# ProPrj___2025-12-14-16-01-24.net
KiCad netlist of a schematic drawn in EasyEDA Pro
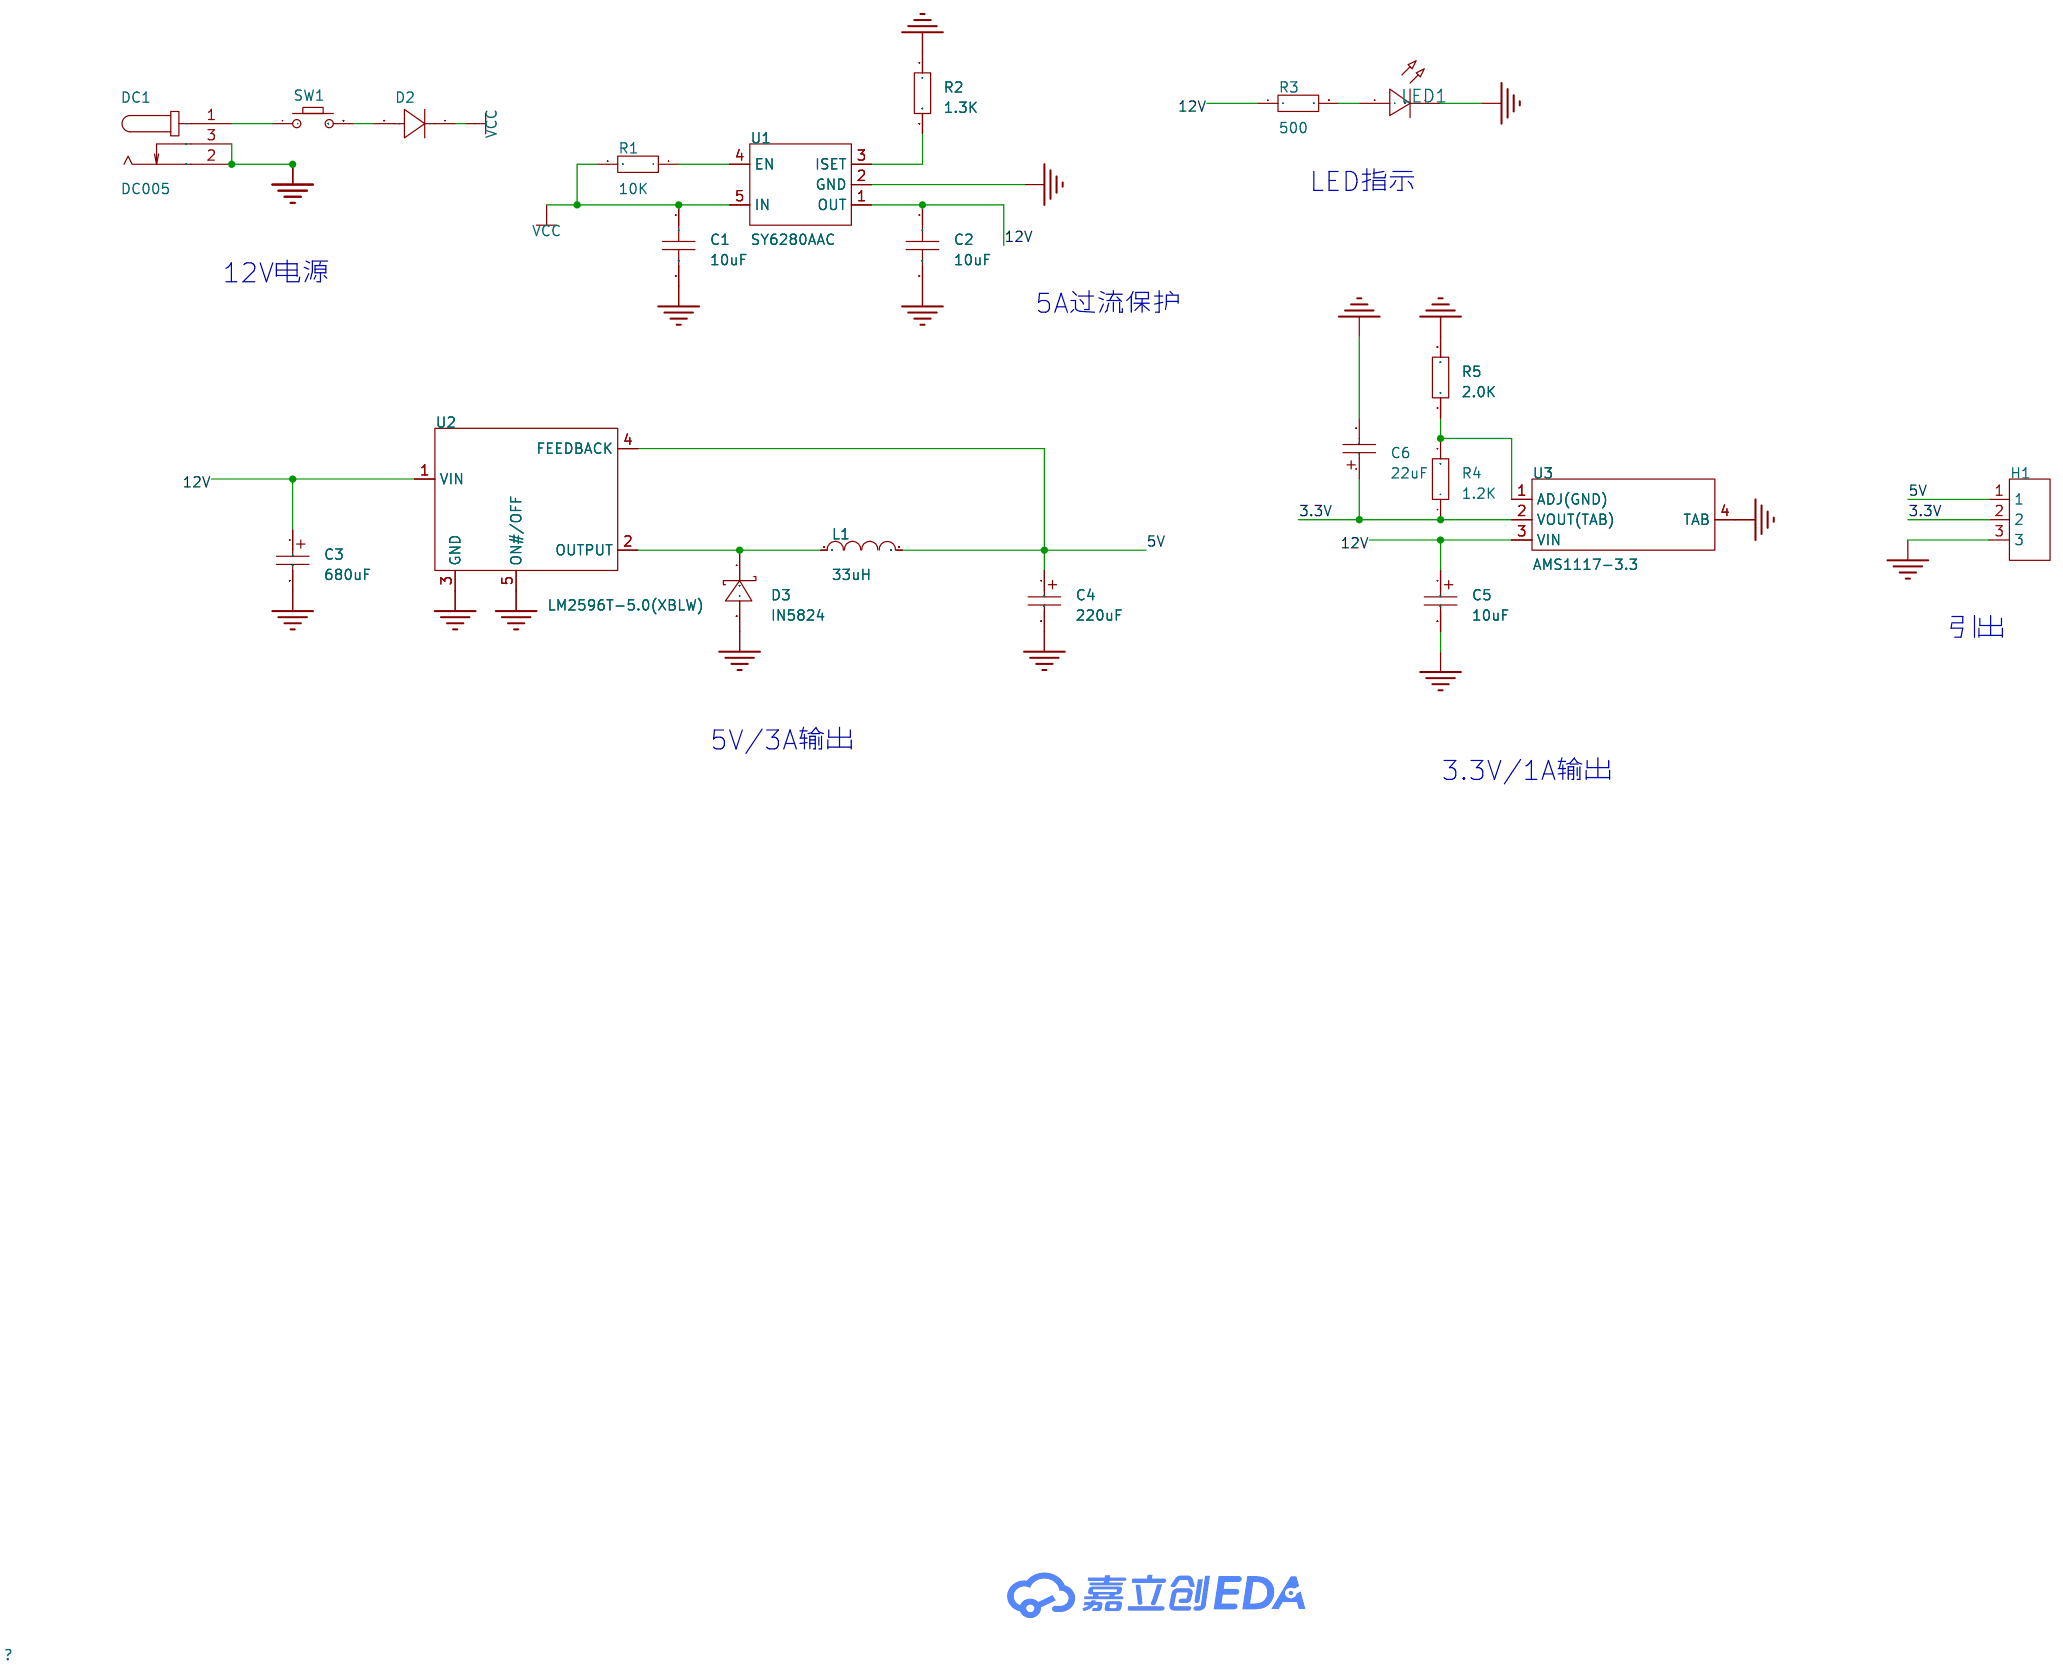
[diagram p0: schematic sheet]

(export (version "E")
  (design (tool "Eeschema 10.0.6"))
  (components
    (comp (ref "C1")
      (value "10uF")
      (footprint "easyedapro:C0603")
      (libsource (lib "easyedapro") (part "Capacitance"))
    )
    (comp (ref "C2")
      (value "10uF")
      (footprint "easyedapro:C0603")
      (libsource (lib "easyedapro") (part "Capacitance"))
    )
    (comp (ref "C3")
      (value "680uF")
      (footprint "easyedapro:C_Ele_SMD_3x5.4mm")
      (libsource (lib "easyedapro") (part "CAP"))
    )
    (comp (ref "C4")
      (value "220uF")
      (footprint "easyedapro:C_Ele_SMD_3x5.4mm")
      (libsource (lib "easyedapro") (part "CAP"))
    )
    (comp (ref "C5")
      (value "10uF")
      (footprint "easyedapro:C_Ele_SMD_3x5.4mm")
      (libsource (lib "easyedapro") (part "CAP"))
    )
    (comp (ref "C6")
      (value "22uF")
      (footprint "easyedapro:C_Ele_SMD_3x5.4mm")
      (libsource (lib "easyedapro") (part "CAP"))
    )
    (comp (ref "D2")
      (value "~")
      (footprint "easyedapro:DO_1N4007")
      (libsource (lib "easyedapro") (part "D_1N4007"))
    )
    (comp (ref "D3")
      (value "IN5824")
      (footprint "easyedapro:SMAF_L3.5-W2.6-LS4.7-RD")
      (libsource (lib "easyedapro") (part "IN5824"))
    )
    (comp (ref "DC1")
      (value "DC005")
      (footprint "easyedapro:DC-IN-TH_DC005")
      (description "连接器类型:DC电源插座;安装方式:弯插;触点内径:2mm;触点外径:6.3mm;额定电流:500mA;额定电压:12V;工作温度:-30°C~+70°C;")
      (fields (field (name "Manufacturer") "SHOU HAN(首韩)"))
      (libsource (lib "easyedapro") (part "DC005_C431533"))
    )
    (comp (ref "H1")
      (value "~")
      (footprint "easyedapro:HDR-TH_3P-P2.54-V-F")
      (libsource (lib "easyedapro") (part "PM254V-11-03-H85"))
    )
    (comp (ref "L1")
      (value "33uH")
      (footprint "easyedapro:L0603")
      (libsource (lib "easyedapro") (part "SDFL1608S100KTF"))
    )
    (comp (ref "LED1")
      (value "~")
      (footprint "easyedapro:LED_0603")
      (libsource (lib "easyedapro") (part "LED_R"))
    )
    (comp (ref "R1") (value "10K") (footprint "easyedapro:R0603") (libsource (lib "easyedapro") (part "电阻")))
    (comp (ref "R2") (value "1.3K") (footprint "easyedapro:R0603") (libsource (lib "easyedapro") (part "电阻")))
    (comp (ref "R3") (value "500") (footprint "easyedapro:R0603") (libsource (lib "easyedapro") (part "电阻")))
    (comp (ref "R4") (value "1.2K") (footprint "easyedapro:R0603") (libsource (lib "easyedapro") (part "电阻")))
    (comp (ref "R5") (value "2.0K") (footprint "easyedapro:R0603") (libsource (lib "easyedapro") (part "电阻")))
    (comp (ref "SW1")
      (value "~")
      (footprint "easyedapro:Key_TH_3.5x6x4.3")
      (libsource (lib "easyedapro") (part "Key_TH_3.5x6x4.3"))
    )
    (comp (ref "U1")
      (value "SY6280AAC")
      (footprint "easyedapro:SOT-23-5_L3.0-W1.7-P0.95-LS2.8-BR")
      (libsource (lib "easyedapro") (part "SY6280AAC_C9900003867"))
    )
    (comp (ref "U2")
      (value "LM2596T-5.0(XBLW)")
      (footprint "easyedapro:TO-220-5L_L10.2-W4.5-P1.71-L")
      (description "功能类型:降压型;工作电压:6V~40V;输出电压:5V;输出电流:3A;输出类型:固定;")
      (fields (field (name "Manufacturer") "XBLW(芯伯乐)"))
      (libsource (lib "easyedapro") (part "LM2596T-5.0(XBLW)"))
    )
    (comp (ref "U3")
      (value "AMS1117-3.3")
      (footprint "easyedapro:SOT-223-4_L6.5-W3.5-P2.30-LS7.0-BR")
      (description "输出类型:固定;工作电压:12V;输出电压:3.3V;输出电流:1A;电源纹波抑制比(PSRR):60dB@(120Hz);输出极性:正极;")
      (fields (field (name "Manufacturer") "UMW(友台半导体)"))
      (libsource (lib "easyedapro") (part "AMS1117-3.3_C347222"))
    )
  )
  (nets
    (net (code "1") (name "/3.3V") (class "Default")
      (node (ref "C6") (pin "1") (pinfunction "1_1") (pintype "input"))
      (node (ref "H1") (pin "2") (pinfunction "2_2") (pintype "unspecified"))
      (node (ref "R4") (pin "1") (pinfunction "1_1") (pintype "input"))
      (node (ref "U3") (pin "2") (pinfunction "VOUT(TAB)_2") (pintype "unspecified"))
    )
    (net (code "2") (name "/5V") (class "Default")
      (node (ref "C4") (pin "1") (pinfunction "1_1") (pintype "input"))
      (node (ref "H1") (pin "1") (pinfunction "1_1") (pintype "unspecified"))
      (node (ref "L1") (pin "2") (pinfunction "2_2") (pintype "unspecified"))
      (node (ref "U2") (pin "4") (pinfunction "FEEDBACK_4") (pintype "unspecified"))
    )
    (net (code "3") (name "/12V") (class "Default")
      (node (ref "C2") (pin "1") (pinfunction "1_1") (pintype "input"))
      (node (ref "C3") (pin "1") (pinfunction "1_1") (pintype "input"))
      (node (ref "C5") (pin "1") (pinfunction "1_1") (pintype "input"))
      (node (ref "R3") (pin "1") (pinfunction "1_1") (pintype "input"))
      (node (ref "U1") (pin "1") (pinfunction "OUT_1") (pintype "unspecified"))
      (node (ref "U2") (pin "1") (pinfunction "VIN_1") (pintype "unspecified"))
      (node (ref "U3") (pin "3") (pinfunction "VIN_3") (pintype "unspecified"))
    )
    (net (code "4") (name "GND") (class "Default")
      (node (ref "C1") (pin "2") (pinfunction "2_2") (pintype "input"))
      (node (ref "C2") (pin "2") (pinfunction "2_2") (pintype "input"))
      (node (ref "C3") (pin "2") (pinfunction "2_2") (pintype "input"))
      (node (ref "C4") (pin "2") (pinfunction "2_2") (pintype "input"))
      (node (ref "C5") (pin "2") (pinfunction "2_2") (pintype "input"))
      (node (ref "C6") (pin "2") (pinfunction "2_2") (pintype "input"))
      (node (ref "D3") (pin "2") (pinfunction "A_2") (pintype "unspecified"))
      (node (ref "DC1") (pin "2") (pinfunction "2_2") (pintype "unspecified"))
      (node (ref "DC1") (pin "3") (pinfunction "3_3") (pintype "unspecified"))
      (node (ref "H1") (pin "3") (pinfunction "3_3") (pintype "unspecified"))
      (node (ref "LED1") (pin "1") (pinfunction "C_1") (pintype "input"))
      (node (ref "R2") (pin "1") (pinfunction "1_1") (pintype "input"))
      (node (ref "R5") (pin "2") (pinfunction "2_2") (pintype "input"))
      (node (ref "U1") (pin "2") (pinfunction "GND_2") (pintype "unspecified"))
      (node (ref "U2") (pin "3") (pinfunction "GND_3") (pintype "unspecified"))
      (node (ref "U2") (pin "5") (pinfunction "ON#/OFF_5") (pintype "unspecified"))
      (node (ref "U3") (pin "4") (pinfunction "TAB_4") (pintype "unspecified"))
    )
    (net (code "5") (name "Net-(D2-A)") (class "Default")
      (node (ref "D2") (pin "2") (pinfunction "A_2") (pintype "input"))
      (node (ref "SW1") (pin "B") (pinfunction "B_B") (pintype "input"))
    )
    (net (code "6") (name "Net-(D3-C)") (class "Default")
      (node (ref "D3") (pin "1") (pinfunction "C_1") (pintype "unspecified"))
      (node (ref "L1") (pin "1") (pinfunction "1_1") (pintype "unspecified"))
      (node (ref "U2") (pin "2") (pinfunction "OUTPUT_2") (pintype "unspecified"))
    )
    (net (code "7") (name "Net-(DC1-Pad1)") (class "Default")
      (node (ref "DC1") (pin "1") (pinfunction "1_1") (pintype "unspecified"))
      (node (ref "SW1") (pin "A") (pinfunction "A_A") (pintype "input"))
    )
    (net (code "8") (name "Net-(LED1-A)") (class "Default")
      (node (ref "LED1") (pin "2") (pinfunction "A_2") (pintype "input"))
      (node (ref "R3") (pin "2") (pinfunction "2_2") (pintype "input"))
    )
    (net (code "9") (name "Net-(U1-EN)") (class "Default")
      (node (ref "R1") (pin "1") (pinfunction "1_1") (pintype "input"))
      (node (ref "U1") (pin "4") (pinfunction "EN_4") (pintype "unspecified"))
    )
    (net (code "10") (name "Net-(U1-ISET)") (class "Default")
      (node (ref "R2") (pin "2") (pinfunction "2_2") (pintype "input"))
      (node (ref "U1") (pin "3") (pinfunction "ISET_3") (pintype "unspecified"))
    )
    (net (code "11") (name "Net-(U3-ADJ(GND))") (class "Default")
      (node (ref "R4") (pin "2") (pinfunction "2_2") (pintype "input"))
      (node (ref "R5") (pin "1") (pinfunction "1_1") (pintype "input"))
      (node (ref "U3") (pin "1") (pinfunction "ADJ(GND)_1") (pintype "unspecified"))
    )
    (net (code "12") (name "VCC") (class "Default")
      (node (ref "C1") (pin "1") (pinfunction "1_1") (pintype "input"))
      (node (ref "D2") (pin "1") (pinfunction "K_1") (pintype "input"))
      (node (ref "R1") (pin "2") (pinfunction "2_2") (pintype "input"))
      (node (ref "U1") (pin "5") (pinfunction "IN_5") (pintype "unspecified"))
    )
  )
)
